# Rauchmelder_2_2C.net
KiCad netlist of a schematic drawn in EAGLE
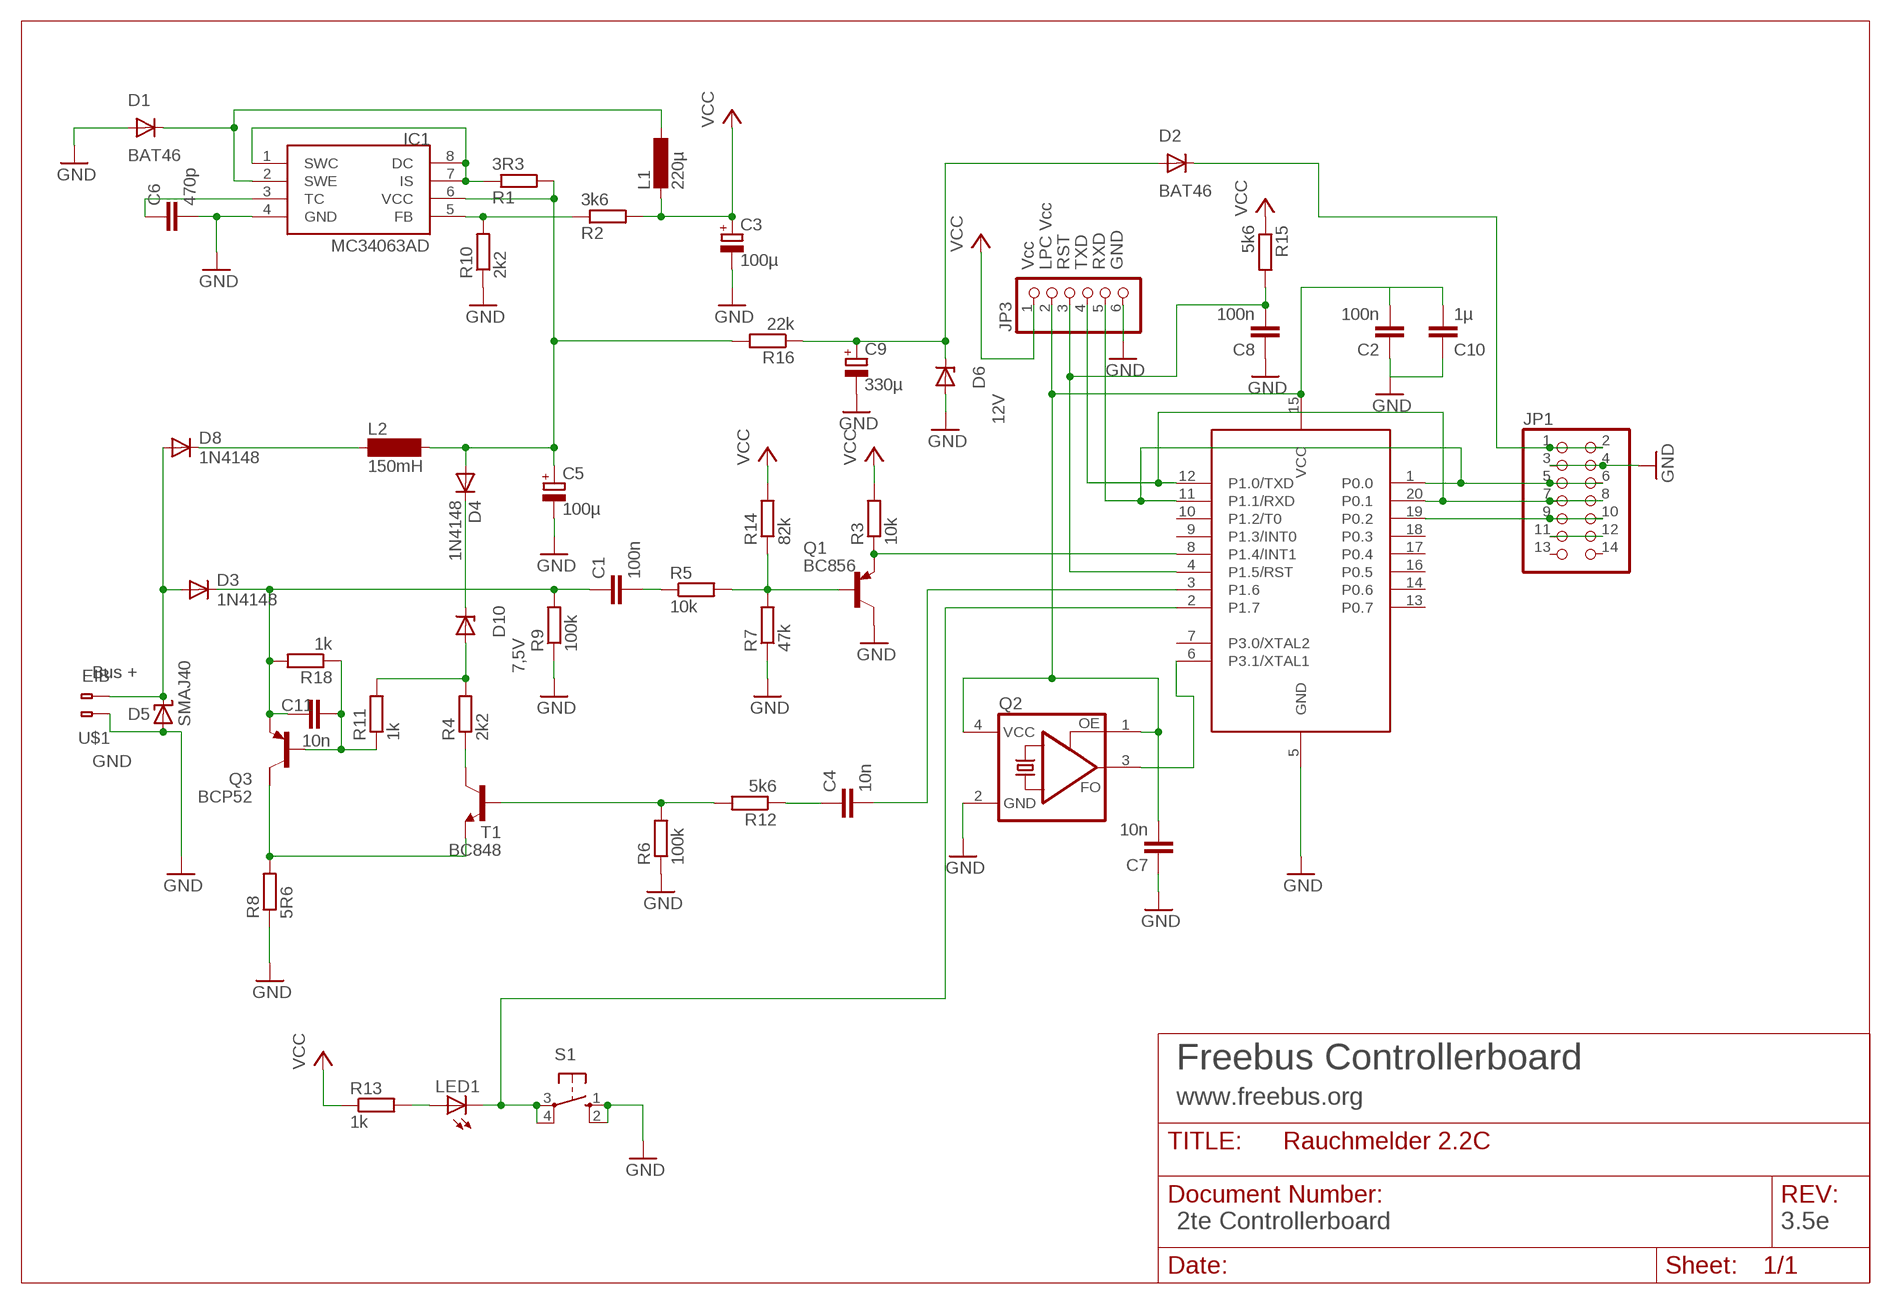
[diagram p0: schematic, sheet 1]

(export (version "E")
  (design (tool "Eeschema 10.0.6"))
  (components
    (comp (ref "C1")
      (value "100n")
      (footprint "eagle-import:C1206")
      (libsource (lib "eagle-import") (part "C-EUC1206"))
    )
    (comp (ref "C2")
      (value "100n")
      (footprint "eagle-import:C1206")
      (libsource (lib "eagle-import") (part "C-EUC1206"))
    )
    (comp (ref "C3")
      (value "100µ")
      (footprint "eagle-import:SANYO-OSCON_SMD_B6")
      (libsource (lib "eagle-import") (part "CPOL-EUSANYO_SMD_B6"))
    )
    (comp (ref "C4")
      (value "10n")
      (footprint "eagle-import:C1206")
      (libsource (lib "eagle-import") (part "C-EUC1206"))
    )
    (comp (ref "C5")
      (value "100µ")
      (footprint "eagle-import:SANYO-OSCON_SMD_C6")
      (libsource (lib "eagle-import") (part "CPOL-EUSANYO_SMD_C6"))
    )
    (comp (ref "C6")
      (value "470p")
      (footprint "eagle-import:C1206")
      (libsource (lib "eagle-import") (part "C-EUC1206"))
    )
    (comp (ref "C7")
      (value "10n")
      (footprint "eagle-import:C1206")
      (libsource (lib "eagle-import") (part "C-EUC1206"))
    )
    (comp (ref "C8")
      (value "100n")
      (footprint "eagle-import:C1206")
      (libsource (lib "eagle-import") (part "C-EUC1206"))
    )
    (comp (ref "C9")
      (value "330µ")
      (footprint "eagle-import:E3,5-8")
      (libsource (lib "eagle-import") (part "CPOL-EUE3.5-8"))
    )
    (comp (ref "C10")
      (value "1µ")
      (footprint "eagle-import:C1206")
      (libsource (lib "eagle-import") (part "C-EUC1206"))
    )
    (comp (ref "C11")
      (value "10n")
      (footprint "eagle-import:C1206")
      (libsource (lib "eagle-import") (part "C-EUC1206"))
    )
    (comp (ref "D1")
      (value "BAT46")
      (footprint "eagle-import:MINIMELF")
      (libsource (lib "eagle-import") (part "DIODE-MINIMELF"))
    )
    (comp (ref "D2")
      (value "BAT46")
      (footprint "eagle-import:MINIMELF")
      (libsource (lib "eagle-import") (part "DIODE-MINIMELF"))
    )
    (comp (ref "D3")
      (value "1N4148")
      (footprint "eagle-import:MINIMELF")
      (libsource (lib "eagle-import") (part "DIODE-MINIMELF"))
    )
    (comp (ref "D4")
      (value "1N4148")
      (footprint "eagle-import:MINIMELF")
      (libsource (lib "eagle-import") (part "DIODE-MINIMELF"))
    )
    (comp (ref "D5")
      (value "SMAJ40")
      (footprint "eagle-import:SMBJ")
      (libsource (lib "eagle-import") (part "SUPPRESSOR-SMBJ"))
    )
    (comp (ref "D6")
      (value "12V")
      (footprint "eagle-import:MINIMELF")
      (libsource (lib "eagle-import") (part "ZPD"))
    )
    (comp (ref "D8")
      (value "1N4148")
      (footprint "eagle-import:MINIMELF")
      (libsource (lib "eagle-import") (part "DIODE-MINIMELF"))
    )
    (comp (ref "D10")
      (value "7,5V")
      (footprint "eagle-import:MINIMELF")
      (libsource (lib "eagle-import") (part "ZPD"))
    )
    (comp (ref "IC1")
      (value "MC34063AD")
      (footprint "eagle-import:SOIC8")
      (libsource (lib "eagle-import") (part "MC34063AD"))
    )
    (comp (ref "IC3")
      (value "LPC922FDH")
      (footprint "eagle-import:TSSOP20")
      (libsource (lib "eagle-import") (part "LPC922FDH"))
    )
    (comp (ref "JP1")
      (value "PINHD-2X7")
      (footprint "eagle-import:2X07")
      (libsource (lib "eagle-import") (part "PINHD-2X7"))
    )
    (comp (ref "JP3")
      (value "PINHD-1X6")
      (footprint "eagle-import:1X06")
      (libsource (lib "eagle-import") (part "PINHD-1X6"))
    )
    (comp (ref "L1")
      (value "220µ")
      (footprint "eagle-import:0207_10")
      (libsource (lib "eagle-import") (part "L-EU0207/10"))
    )
    (comp (ref "L2")
      (value "150mH")
      (footprint "eagle-import:BS11")
      (libsource (lib "eagle-import") (part "BS11"))
    )
    (comp (ref "LED1")
      (value "LED3MM")
      (footprint "eagle-import:LED3MM")
      (libsource (lib "eagle-import") (part "LED3MM"))
    )
    (comp (ref "Q1")
      (value "BC856")
      (footprint "eagle-import:SOT23-BEC")
      (libsource (lib "eagle-import") (part "BC856SMDALT1"))
    )
    (comp (ref "Q2")
      (value "ASFL")
      (footprint "eagle-import:ASF")
      (libsource (lib "eagle-import") (part "ASFL"))
    )
    (comp (ref "Q3")
      (value "BCP52")
      (footprint "eagle-import:SOT223")
      (libsource (lib "eagle-import") (part "FZT753SMD"))
    )
    (comp (ref "R1")
      (value "3R3")
      (footprint "eagle-import:R1206")
      (libsource (lib "eagle-import") (part "R-EU_R1206"))
    )
    (comp (ref "R2")
      (value "3k6")
      (footprint "eagle-import:R1206")
      (libsource (lib "eagle-import") (part "R-EU_R1206"))
    )
    (comp (ref "R3")
      (value "10k")
      (footprint "eagle-import:R1206")
      (libsource (lib "eagle-import") (part "R-EU_R1206"))
    )
    (comp (ref "R4")
      (value "2k2")
      (footprint "eagle-import:R1206")
      (libsource (lib "eagle-import") (part "R-EU_R1206"))
    )
    (comp (ref "R5")
      (value "10k")
      (footprint "eagle-import:R1206")
      (libsource (lib "eagle-import") (part "R-EU_R1206"))
    )
    (comp (ref "R6")
      (value "100k")
      (footprint "eagle-import:R1206")
      (libsource (lib "eagle-import") (part "R-EU_R1206"))
    )
    (comp (ref "R7")
      (value "47k")
      (footprint "eagle-import:R1206")
      (libsource (lib "eagle-import") (part "R-EU_R1206"))
    )
    (comp (ref "R8")
      (value "5R6")
      (footprint "eagle-import:R1206")
      (libsource (lib "eagle-import") (part "R-EU_R1206"))
    )
    (comp (ref "R9")
      (value "100k")
      (footprint "eagle-import:R1206")
      (libsource (lib "eagle-import") (part "R-EU_R1206"))
    )
    (comp (ref "R10")
      (value "2k2")
      (footprint "eagle-import:R1206")
      (libsource (lib "eagle-import") (part "R-EU_R1206"))
    )
    (comp (ref "R11")
      (value "1k")
      (footprint "eagle-import:R1206")
      (libsource (lib "eagle-import") (part "R-EU_R1206"))
    )
    (comp (ref "R12")
      (value "5k6")
      (footprint "eagle-import:R1206")
      (libsource (lib "eagle-import") (part "R-EU_R1206"))
    )
    (comp (ref "R13")
      (value "1k")
      (footprint "eagle-import:R1206")
      (libsource (lib "eagle-import") (part "R-EU_R1206"))
    )
    (comp (ref "R14")
      (value "82k")
      (footprint "eagle-import:R1206")
      (libsource (lib "eagle-import") (part "R-EU_R1206"))
    )
    (comp (ref "R15")
      (value "5k6")
      (footprint "eagle-import:R1206")
      (libsource (lib "eagle-import") (part "R-EU_R1206"))
    )
    (comp (ref "R16")
      (value "22k")
      (footprint "eagle-import:R1206")
      (libsource (lib "eagle-import") (part "R-EU_R1206"))
    )
    (comp (ref "R18")
      (value "1k")
      (footprint "eagle-import:R1206")
      (libsource (lib "eagle-import") (part "R-EU_R1206"))
    )
    (comp (ref "S1")
      (value "10-XX")
      (footprint "eagle-import:B3F-10XX")
      (libsource (lib "eagle-import") (part "10-XX"))
    )
    (comp (ref "T1")
      (value "BC848")
      (footprint "eagle-import:SOT23")
      (libsource (lib "eagle-import") (part "BC848"))
    )
    (comp (ref "U$1")
      (value "EIB")
      (footprint "eagle-import:BUSKLEMME243-724")
      (libsource (lib "eagle-import") (part "EIB"))
    )
  )
  (nets
    (net (code "1") (name "GND") (class "Default")
      (node (ref "C10") (pin "1") (pinfunction "1_1") (pintype "passive"))
      (node (ref "C2") (pin "1") (pinfunction "1_1") (pintype "passive"))
      (node (ref "C3") (pin "-") (pinfunction "-_-") (pintype "passive"))
      (node (ref "C5") (pin "-") (pinfunction "-_-") (pintype "passive"))
      (node (ref "C6") (pin "2") (pinfunction "2_2") (pintype "passive"))
      (node (ref "C7") (pin "1") (pinfunction "1_1") (pintype "passive"))
      (node (ref "C8") (pin "1") (pinfunction "1_1") (pintype "passive"))
      (node (ref "C9") (pin "-") (pinfunction "-_-") (pintype "passive"))
      (node (ref "D1") (pin "A") (pinfunction "A_A") (pintype "passive"))
      (node (ref "D5") (pin "A") (pinfunction "A_A") (pintype "passive"))
      (node (ref "D6") (pin "A") (pinfunction "A_A") (pintype "passive"))
      (node (ref "IC1") (pin "4") (pinfunction "GND_4") (pintype "passive"))
      (node (ref "IC3") (pin "5") (pinfunction "GND_5") (pintype "bidirectional"))
      (node (ref "JP1") (pin "3") (pinfunction "3_3") (pintype "passive"))
      (node (ref "JP1") (pin "4") (pinfunction "4_4") (pintype "passive"))
      (node (ref "JP3") (pin "6") (pinfunction "6_6") (pintype "passive"))
      (node (ref "Q1") (pin "C") (pinfunction "C_C") (pintype "passive"))
      (node (ref "Q2") (pin "2") (pinfunction "GND_2") (pintype "power_in"))
      (node (ref "R10") (pin "1") (pinfunction "1_1") (pintype "passive"))
      (node (ref "R6") (pin "1") (pinfunction "1_1") (pintype "passive"))
      (node (ref "R7") (pin "1") (pinfunction "1_1") (pintype "passive"))
      (node (ref "R8") (pin "1") (pinfunction "1_1") (pintype "passive"))
      (node (ref "R9") (pin "1") (pinfunction "1_1") (pintype "passive"))
      (node (ref "S1") (pin "1") (pinfunction "S_1") (pintype "passive"))
      (node (ref "S1") (pin "2") (pinfunction "S1_2") (pintype "passive"))
      (node (ref "U$1") (pin "1") (pinfunction "B-1_1") (pintype "passive"))
    )
    (net (code "2") (name "Net-(C1-Pad2)") (class "Default")
      (node (ref "C1") (pin "2") (pinfunction "2_2") (pintype "passive"))
      (node (ref "R5") (pin "1") (pinfunction "1_1") (pintype "passive"))
    )
    (net (code "3") (name "Net-(C4-Pad1)") (class "Default")
      (node (ref "C4") (pin "1") (pinfunction "1_1") (pintype "passive"))
      (node (ref "R12") (pin "1") (pinfunction "1_1") (pintype "passive"))
    )
    (net (code "4") (name "Net-(C9-Pad+)") (class "Default")
      (node (ref "C9") (pin "+") (pinfunction "+_+") (pintype "passive"))
      (node (ref "D2") (pin "A") (pinfunction "A_A") (pintype "passive"))
      (node (ref "D6") (pin "C") (pinfunction "C_C") (pintype "passive"))
      (node (ref "R16") (pin "1") (pinfunction "1_1") (pintype "passive"))
    )
    (net (code "5") (name "Net-(D2-PadC)") (class "Default")
      (node (ref "D2") (pin "C") (pinfunction "C_C") (pintype "passive"))
      (node (ref "JP1") (pin "1") (pinfunction "1_1") (pintype "passive"))
      (node (ref "JP1") (pin "2") (pinfunction "2_2") (pintype "passive"))
    )
    (net (code "6") (name "Net-(D8-PadC)") (class "Default")
      (node (ref "D8") (pin "C") (pinfunction "C_C") (pintype "passive"))
      (node (ref "L2") (pin "1") (pinfunction "1_1") (pintype "passive"))
    )
    (net (code "7") (name "Net-(D10-PadA)") (class "Default")
      (node (ref "D10") (pin "A") (pinfunction "A_A") (pintype "passive"))
      (node (ref "R11") (pin "2") (pinfunction "2_2") (pintype "passive"))
      (node (ref "R4") (pin "2") (pinfunction "2_2") (pintype "passive"))
    )
    (net (code "8") (name "Net-(D10-PadC)") (class "Default")
      (node (ref "D10") (pin "C") (pinfunction "C_C") (pintype "passive"))
      (node (ref "D4") (pin "C") (pinfunction "C_C") (pintype "passive"))
    )
    (net (code "9") (name "Net-(IC1-DC)") (class "Default")
      (node (ref "IC1") (pin "1") (pinfunction "SWC_1") (pintype "passive"))
      (node (ref "IC1") (pin "7") (pinfunction "IS_7") (pintype "passive"))
      (node (ref "IC1") (pin "8") (pinfunction "DC_8") (pintype "passive"))
      (node (ref "R1") (pin "1") (pinfunction "1_1") (pintype "passive"))
    )
    (net (code "10") (name "Net-(IC1-FB)") (class "Default")
      (node (ref "IC1") (pin "5") (pinfunction "FB_5") (pintype "passive"))
      (node (ref "R10") (pin "2") (pinfunction "2_2") (pintype "passive"))
      (node (ref "R2") (pin "1") (pinfunction "1_1") (pintype "passive"))
    )
    (net (code "11") (name "Net-(IC1-SWE)") (class "Default")
      (node (ref "D1") (pin "C") (pinfunction "C_C") (pintype "passive"))
      (node (ref "IC1") (pin "2") (pinfunction "SWE_2") (pintype "passive"))
      (node (ref "L1") (pin "1") (pinfunction "1_1") (pintype "passive"))
    )
    (net (code "12") (name "Net-(IC1-TC)") (class "Default")
      (node (ref "C6") (pin "1") (pinfunction "1_1") (pintype "passive"))
      (node (ref "IC1") (pin "3") (pinfunction "TC_3") (pintype "passive"))
    )
    (net (code "13") (name "Net-(IC1-VCC)") (class "Default")
      (node (ref "C5") (pin "+") (pinfunction "+_+") (pintype "passive"))
      (node (ref "D4") (pin "A") (pinfunction "A_A") (pintype "passive"))
      (node (ref "IC1") (pin "6") (pinfunction "VCC_6") (pintype "passive"))
      (node (ref "L2") (pin "2") (pinfunction "2_2") (pintype "passive"))
      (node (ref "R1") (pin "2") (pinfunction "2_2") (pintype "passive"))
      (node (ref "R16") (pin "2") (pinfunction "2_2") (pintype "passive"))
    )
    (net (code "14") (name "Net-(IC3-P0.0)") (class "Default")
      (node (ref "IC3") (pin "1") (pinfunction "P0.0_1") (pintype "bidirectional"))
      (node (ref "IC3") (pin "11") (pinfunction "P1.1/RXD_11") (pintype "bidirectional"))
      (node (ref "JP1") (pin "5") (pinfunction "5_5") (pintype "passive"))
      (node (ref "JP1") (pin "6") (pinfunction "6_6") (pintype "passive"))
      (node (ref "JP3") (pin "5") (pinfunction "5_5") (pintype "passive"))
    )
    (net (code "15") (name "Net-(IC3-P0.1)") (class "Default")
      (node (ref "IC3") (pin "12") (pinfunction "P1.0/TXD_12") (pintype "bidirectional"))
      (node (ref "IC3") (pin "20") (pinfunction "P0.1_20") (pintype "bidirectional"))
      (node (ref "JP1") (pin "7") (pinfunction "7_7") (pintype "passive"))
      (node (ref "JP1") (pin "8") (pinfunction "8_8") (pintype "passive"))
      (node (ref "JP3") (pin "4") (pinfunction "4_4") (pintype "passive"))
    )
    (net (code "16") (name "Net-(IC3-P0.2)") (class "Default")
      (node (ref "IC3") (pin "19") (pinfunction "P0.2_19") (pintype "bidirectional"))
      (node (ref "JP1") (pin "10") (pinfunction "10_10") (pintype "passive"))
      (node (ref "JP1") (pin "9") (pinfunction "9_9") (pintype "passive"))
    )
    (net (code "17") (name "Net-(IC3-P1.4{slash}INT1)") (class "Default")
      (node (ref "IC3") (pin "8") (pinfunction "P1.4/INT1_8") (pintype "bidirectional"))
      (node (ref "Q1") (pin "E") (pinfunction "E_E") (pintype "passive"))
      (node (ref "R3") (pin "1") (pinfunction "1_1") (pintype "passive"))
    )
    (net (code "18") (name "Net-(IC3-P1.5{slash}RST)") (class "Default")
      (node (ref "C8") (pin "2") (pinfunction "2_2") (pintype "passive"))
      (node (ref "IC3") (pin "4") (pinfunction "P1.5/RST_4") (pintype "bidirectional"))
      (node (ref "JP3") (pin "3") (pinfunction "3_3") (pintype "passive"))
      (node (ref "R15") (pin "2") (pinfunction "2_2") (pintype "passive"))
    )
    (net (code "19") (name "Net-(IC3-P1.6)") (class "Default")
      (node (ref "C4") (pin "2") (pinfunction "2_2") (pintype "passive"))
      (node (ref "IC3") (pin "3") (pinfunction "P1.6_3") (pintype "bidirectional"))
    )
    (net (code "20") (name "Net-(IC3-P1.7)") (class "Default")
      (node (ref "IC3") (pin "2") (pinfunction "P1.7_2") (pintype "bidirectional"))
      (node (ref "LED1") (pin "K") (pinfunction "C_K") (pintype "passive"))
      (node (ref "S1") (pin "3") (pinfunction "P_3") (pintype "passive"))
      (node (ref "S1") (pin "4") (pinfunction "P1_4") (pintype "passive"))
    )
    (net (code "21") (name "Net-(IC3-P3.1{slash}XTAL1)") (class "Default")
      (node (ref "IC3") (pin "6") (pinfunction "P3.1/XTAL1_6") (pintype "bidirectional"))
      (node (ref "Q2") (pin "3") (pinfunction "FO_3") (pintype "output"))
    )
    (net (code "22") (name "Net-(IC3-VCC)") (class "Default")
      (node (ref "C10") (pin "2") (pinfunction "2_2") (pintype "passive"))
      (node (ref "C2") (pin "2") (pinfunction "2_2") (pintype "passive"))
      (node (ref "C7") (pin "2") (pinfunction "2_2") (pintype "passive"))
      (node (ref "IC3") (pin "15") (pinfunction "VCC_15") (pintype "bidirectional"))
      (node (ref "JP3") (pin "2") (pinfunction "2_2") (pintype "passive"))
      (node (ref "Q2") (pin "1") (pinfunction "OE_1") (pintype "input"))
      (node (ref "Q2") (pin "4") (pinfunction "VCC_4") (pintype "power_in"))
    )
    (net (code "23") (name "Net-(JP1-Pad11)") (class "Default")
      (node (ref "JP1") (pin "11") (pinfunction "11_11") (pintype "passive"))
      (node (ref "JP1") (pin "12") (pinfunction "12_12") (pintype "passive"))
    )
    (net (code "24") (name "Net-(LED1-PadA)") (class "Default")
      (node (ref "LED1") (pin "A") (pinfunction "A_A") (pintype "passive"))
      (node (ref "R13") (pin "2") (pinfunction "2_2") (pintype "passive"))
    )
    (net (code "25") (name "Net-(Q1-PadB)") (class "Default")
      (node (ref "Q1") (pin "B") (pinfunction "B_B") (pintype "passive"))
      (node (ref "R14") (pin "1") (pinfunction "1_1") (pintype "passive"))
      (node (ref "R5") (pin "2") (pinfunction "2_2") (pintype "passive"))
      (node (ref "R7") (pin "2") (pinfunction "2_2") (pintype "passive"))
    )
    (net (code "26") (name "Net-(Q3-B)") (class "Default")
      (node (ref "C11") (pin "2") (pinfunction "2_2") (pintype "passive"))
      (node (ref "Q3") (pin "1") (pinfunction "B_1") (pintype "passive"))
      (node (ref "R11") (pin "1") (pinfunction "1_1") (pintype "passive"))
      (node (ref "R18") (pin "1") (pinfunction "1_1") (pintype "passive"))
    )
    (net (code "27") (name "Net-(Q3-C)") (class "Default")
      (node (ref "Q3") (pin "2") (pinfunction "C_2") (pintype "passive"))
      (node (ref "R8") (pin "2") (pinfunction "2_2") (pintype "passive"))
      (node (ref "T1") (pin "2") (pinfunction "E_2") (pintype "passive"))
    )
    (net (code "28") (name "Net-(Q3-E)") (class "Default")
      (node (ref "C1") (pin "1") (pinfunction "1_1") (pintype "passive"))
      (node (ref "C11") (pin "1") (pinfunction "1_1") (pintype "passive"))
      (node (ref "D3") (pin "C") (pinfunction "C_C") (pintype "passive"))
      (node (ref "Q3") (pin "3") (pinfunction "E_3") (pintype "passive"))
      (node (ref "R18") (pin "2") (pinfunction "2_2") (pintype "passive"))
      (node (ref "R9") (pin "2") (pinfunction "2_2") (pintype "passive"))
    )
    (net (code "29") (name "Net-(T1-B)") (class "Default")
      (node (ref "R12") (pin "2") (pinfunction "2_2") (pintype "passive"))
      (node (ref "R6") (pin "2") (pinfunction "2_2") (pintype "passive"))
      (node (ref "T1") (pin "1") (pinfunction "B_1") (pintype "passive"))
    )
    (net (code "30") (name "Net-(T1-C)") (class "Default")
      (node (ref "R4") (pin "1") (pinfunction "1_1") (pintype "passive"))
      (node (ref "T1") (pin "3") (pinfunction "C_3") (pintype "passive"))
    )
    (net (code "31") (name "Net-(U$1-B-2)") (class "Default")
      (node (ref "D3") (pin "A") (pinfunction "A_A") (pintype "passive"))
      (node (ref "D5") (pin "C") (pinfunction "C_C") (pintype "passive"))
      (node (ref "D8") (pin "A") (pinfunction "A_A") (pintype "passive"))
      (node (ref "U$1") (pin "2") (pinfunction "B-2_2") (pintype "passive"))
    )
    (net (code "32") (name "VCC") (class "Default")
      (node (ref "C3") (pin "+") (pinfunction "+_+") (pintype "passive"))
      (node (ref "JP3") (pin "1") (pinfunction "1_1") (pintype "passive"))
      (node (ref "L1") (pin "2") (pinfunction "2_2") (pintype "passive"))
      (node (ref "R13") (pin "1") (pinfunction "1_1") (pintype "passive"))
      (node (ref "R14") (pin "2") (pinfunction "2_2") (pintype "passive"))
      (node (ref "R15") (pin "1") (pinfunction "1_1") (pintype "passive"))
      (node (ref "R2") (pin "2") (pinfunction "2_2") (pintype "passive"))
      (node (ref "R3") (pin "2") (pinfunction "2_2") (pintype "passive"))
    )
    (net (code "33") (name "unconnected-(IC3-P0.3-Pad18)") (class "Default")
      (node (ref "IC3") (pin "18") (pinfunction "P0.3_18") (pintype "bidirectional"))
    )
    (net (code "34") (name "unconnected-(IC3-P0.4-Pad17)") (class "Default")
      (node (ref "IC3") (pin "17") (pinfunction "P0.4_17") (pintype "bidirectional"))
    )
    (net (code "35") (name "unconnected-(IC3-P0.5-Pad16)") (class "Default")
      (node (ref "IC3") (pin "16") (pinfunction "P0.5_16") (pintype "bidirectional"))
    )
    (net (code "36") (name "unconnected-(IC3-P0.6-Pad14)") (class "Default")
      (node (ref "IC3") (pin "14") (pinfunction "P0.6_14") (pintype "bidirectional"))
    )
    (net (code "37") (name "unconnected-(IC3-P0.7-Pad13)") (class "Default")
      (node (ref "IC3") (pin "13") (pinfunction "P0.7_13") (pintype "bidirectional"))
    )
    (net (code "38") (name "unconnected-(IC3-P1.2{slash}T0-Pad10)") (class "Default")
      (node (ref "IC3") (pin "10") (pinfunction "P1.2/T0_10") (pintype "bidirectional"))
    )
    (net (code "39") (name "unconnected-(IC3-P1.3{slash}INT0-Pad9)") (class "Default")
      (node (ref "IC3") (pin "9") (pinfunction "P1.3/INT0_9") (pintype "bidirectional"))
    )
    (net (code "40") (name "unconnected-(IC3-P3.0{slash}XTAL2-Pad7)") (class "Default")
      (node (ref "IC3") (pin "7") (pinfunction "P3.0/XTAL2_7") (pintype "bidirectional"))
    )
    (net (code "41") (name "unconnected-(JP1-Pad13)") (class "Default")
      (node (ref "JP1") (pin "13") (pinfunction "13_13") (pintype "passive"))
    )
    (net (code "42") (name "unconnected-(JP1-Pad14)") (class "Default")
      (node (ref "JP1") (pin "14") (pinfunction "14_14") (pintype "passive"))
    )
    (net (code "43") (name "unconnected-(Q3-C{slash}-Pad4)") (class "Default")
      (node (ref "Q3") (pin "4") (pinfunction "C/_4") (pintype "passive"))
    )
  )
)
